# Distance_and_PhotoElectric.net
KiCad netlist of a schematic drawn in Altium Designer
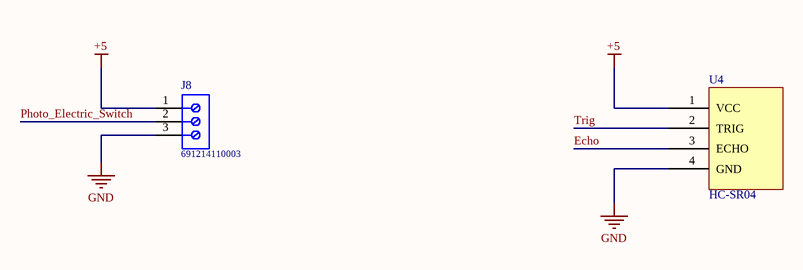
[diagram p0: Distance and PhotoElectric.SchDoc]

(export (version "E")
  (design (tool "Eeschema 10.0.6"))
  (components
    (comp (ref "J8")
      (value "691214110003")
      (footprint "691214110003")
      (description "Serie 2141 - 3.50 mm Horizontal Entry Modular with Rising Cage Clamp WR-TBL, 3 pin")
      (fields (field (name "MANUFACTURER") "Wurth Elektronik") (field (name "PUBLISHER") "WurthElektronik"))
      (libsource (lib "Altium Content Vault") (part "WE-CN-1P-F-TB3"))
    )
    (comp (ref "U4")
      (value "HC-SR04")
      (footprint "HC-SR04")
      (description "5V 15mA Distance Sensor THT Arduino Sensor")
      (libsource (lib "User_Library") (part "HC - SR04"))
    )
  )
  (nets
    (net (code "1") (name "+5") (class "Default")
      (node (ref "J8") (pin "1") (pinfunction "1_1") (pintype "passive"))
      (node (ref "U4") (pin "1") (pinfunction "VCC_1") (pintype "power_in"))
    )
    (net (code "2") (name "/Echo") (class "Default")
      (node (ref "U4") (pin "3") (pinfunction "ECHO_3") (pintype "power_in"))
    )
    (net (code "3") (name "/Photo_Electric_Switch") (class "Default")
      (node (ref "J8") (pin "2") (pinfunction "2_2") (pintype "passive"))
    )
    (net (code "4") (name "/Trig") (class "Default")
      (node (ref "U4") (pin "2") (pinfunction "TRIG_2") (pintype "power_in"))
    )
    (net (code "5") (name "GND") (class "Default")
      (node (ref "J8") (pin "3") (pinfunction "3_3") (pintype "passive"))
      (node (ref "U4") (pin "4") (pinfunction "GND_4") (pintype "power_in"))
    )
  )
)
